# crossbar.net
KiCad netlist of a schematic drawn in Altium Designer
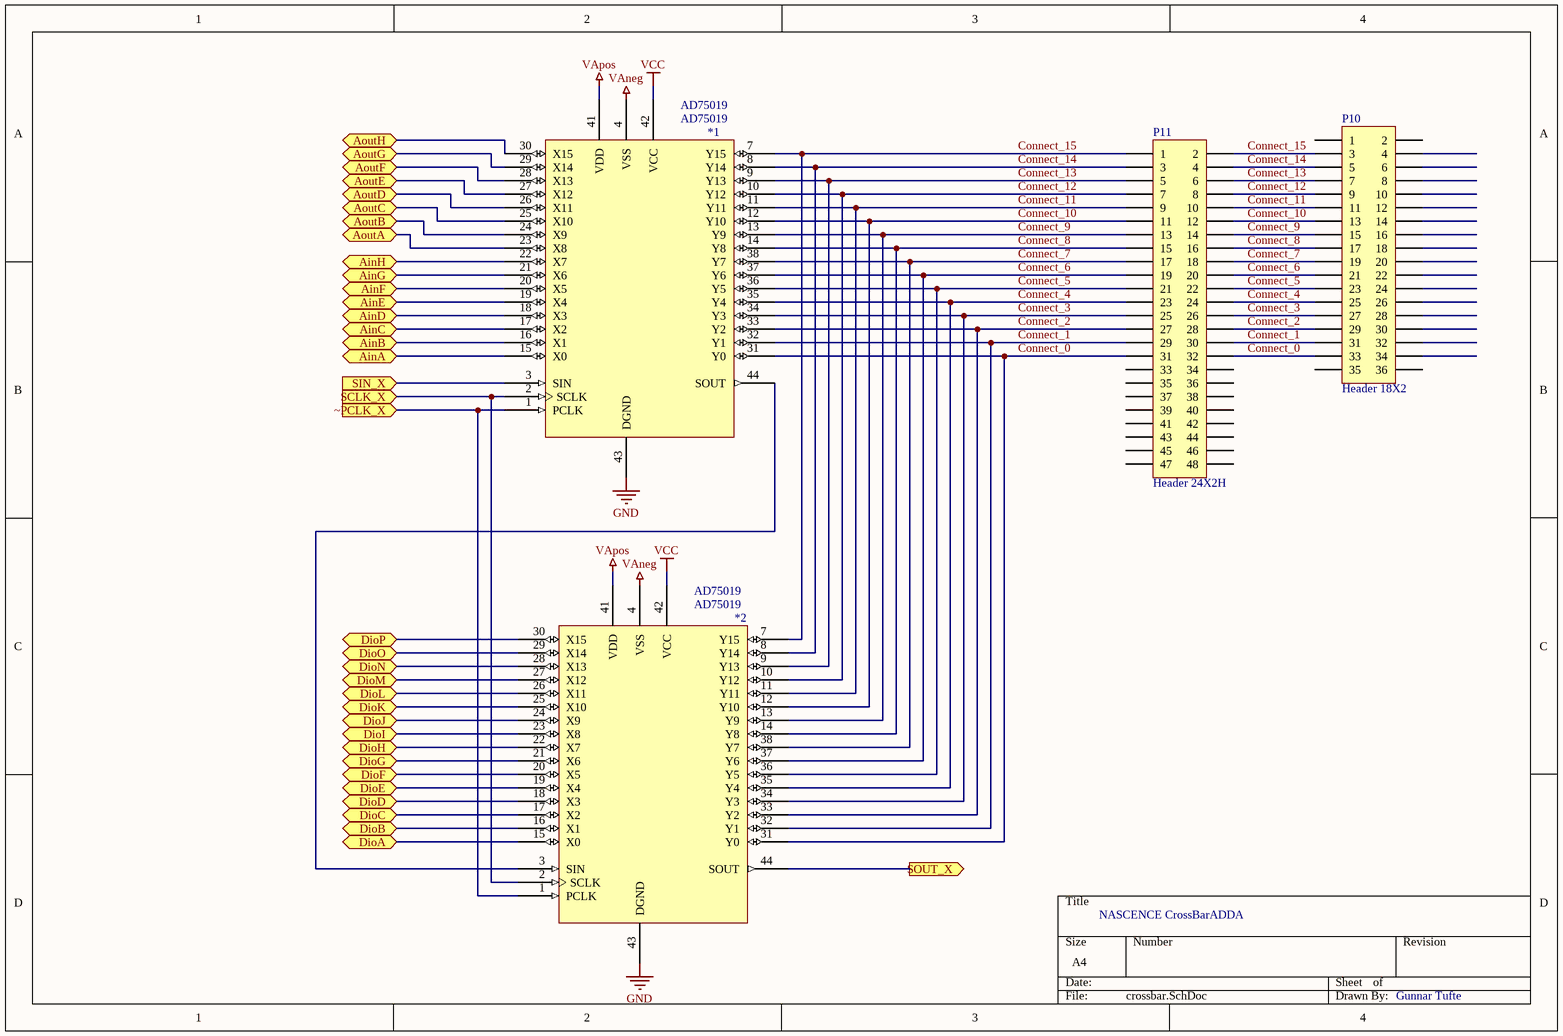
[diagram p0: crossbar.SchDoc]

(export (version "E")
  (design (tool "Eeschema 10.0.6"))
  (components
    (comp (ref "*1")
      (value "AD75019")
      (footprint "PLCC-44AL")
      (description "crosspoint 16x16")
      (fields (field (name "ALTIUM_UNNAMED_1") "AD75019"))
      (libsource (lib "GT_Schlib1") (part "Component_1"))
    )
    (comp (ref "*2")
      (value "AD75019")
      (footprint "PLCC-44AL")
      (description "crosspoint 16x16")
      (fields (field (name "ALTIUM_UNNAMED_1") "AD75019"))
      (libsource (lib "GT_Schlib1") (part "Component_1"))
    )
    (comp (ref "P10")
      (value "Header 18X2")
      (footprint "HDR2X18")
      (description "Header, 18-Pin, Dual row")
      (fields (field (name "PUBLISHER") "Altium Limited"))
      (libsource (lib "Miscellaneous Connectors") (part "Header 18X2"))
    )
    (comp (ref "P11")
      (value "Header 24X2H")
      (footprint "HDR2X24H")
      (description "Header, 24-Pin, Dual row, Right Angle")
      (fields (field (name "PUBLISHER") "Altium Limited"))
      (libsource (lib "Miscellaneous Connectors") (part "Header 24X2H"))
    )
  )
  (nets
    (net (code "1") (name "/AinA") (class "Default")
      (node (ref "*1") (pin "15") (pinfunction "X0_15") (pintype "bidirectional"))
    )
    (net (code "2") (name "/AinB") (class "Default")
      (node (ref "*1") (pin "16") (pinfunction "X1_16") (pintype "bidirectional"))
    )
    (net (code "3") (name "/AinC") (class "Default")
      (node (ref "*1") (pin "17") (pinfunction "X2_17") (pintype "bidirectional"))
    )
    (net (code "4") (name "/AinD") (class "Default")
      (node (ref "*1") (pin "18") (pinfunction "X3_18") (pintype "bidirectional"))
    )
    (net (code "5") (name "/AinE") (class "Default")
      (node (ref "*1") (pin "19") (pinfunction "X4_19") (pintype "bidirectional"))
    )
    (net (code "6") (name "/AinF") (class "Default")
      (node (ref "*1") (pin "20") (pinfunction "X5_20") (pintype "bidirectional"))
    )
    (net (code "7") (name "/AinG") (class "Default")
      (node (ref "*1") (pin "21") (pinfunction "X6_21") (pintype "bidirectional"))
    )
    (net (code "8") (name "/AinH") (class "Default")
      (node (ref "*1") (pin "22") (pinfunction "X7_22") (pintype "bidirectional"))
    )
    (net (code "9") (name "/AoutA") (class "Default")
      (node (ref "*1") (pin "23") (pinfunction "X8_23") (pintype "bidirectional"))
    )
    (net (code "10") (name "/AoutB") (class "Default")
      (node (ref "*1") (pin "24") (pinfunction "X9_24") (pintype "bidirectional"))
    )
    (net (code "11") (name "/AoutC") (class "Default")
      (node (ref "*1") (pin "25") (pinfunction "X10_25") (pintype "bidirectional"))
    )
    (net (code "12") (name "/AoutD") (class "Default")
      (node (ref "*1") (pin "26") (pinfunction "X11_26") (pintype "bidirectional"))
    )
    (net (code "13") (name "/AoutE") (class "Default")
      (node (ref "*1") (pin "27") (pinfunction "X12_27") (pintype "bidirectional"))
    )
    (net (code "14") (name "/AoutF") (class "Default")
      (node (ref "*1") (pin "28") (pinfunction "X13_28") (pintype "bidirectional"))
    )
    (net (code "15") (name "/AoutG") (class "Default")
      (node (ref "*1") (pin "29") (pinfunction "X14_29") (pintype "bidirectional"))
    )
    (net (code "16") (name "/AoutH") (class "Default")
      (node (ref "*1") (pin "30") (pinfunction "X15_30") (pintype "bidirectional"))
    )
    (net (code "17") (name "/Connect_0") (class "Default")
      (node (ref "*1") (pin "31") (pinfunction "Y0_31") (pintype "bidirectional"))
      (node (ref "*2") (pin "31") (pinfunction "Y0_31") (pintype "bidirectional"))
      (node (ref "P10") (pin "33") (pinfunction "33_33") (pintype "passive"))
      (node (ref "P11") (pin "31") (pinfunction "31_31") (pintype "passive"))
      (node (ref "P11") (pin "32") (pinfunction "32_32") (pintype "passive"))
    )
    (net (code "18") (name "/Connect_1") (class "Default")
      (node (ref "*1") (pin "32") (pinfunction "Y1_32") (pintype "bidirectional"))
      (node (ref "*2") (pin "32") (pinfunction "Y1_32") (pintype "bidirectional"))
      (node (ref "P10") (pin "31") (pinfunction "31_31") (pintype "passive"))
      (node (ref "P11") (pin "29") (pinfunction "29_29") (pintype "passive"))
      (node (ref "P11") (pin "30") (pinfunction "30_30") (pintype "passive"))
    )
    (net (code "19") (name "/Connect_2") (class "Default")
      (node (ref "*1") (pin "33") (pinfunction "Y2_33") (pintype "bidirectional"))
      (node (ref "*2") (pin "33") (pinfunction "Y2_33") (pintype "bidirectional"))
      (node (ref "P10") (pin "29") (pinfunction "29_29") (pintype "passive"))
      (node (ref "P11") (pin "27") (pinfunction "27_27") (pintype "passive"))
      (node (ref "P11") (pin "28") (pinfunction "28_28") (pintype "passive"))
    )
    (net (code "20") (name "/Connect_3") (class "Default")
      (node (ref "*1") (pin "34") (pinfunction "Y3_34") (pintype "bidirectional"))
      (node (ref "*2") (pin "34") (pinfunction "Y3_34") (pintype "bidirectional"))
      (node (ref "P10") (pin "27") (pinfunction "27_27") (pintype "passive"))
      (node (ref "P11") (pin "25") (pinfunction "25_25") (pintype "passive"))
      (node (ref "P11") (pin "26") (pinfunction "26_26") (pintype "passive"))
    )
    (net (code "21") (name "/Connect_4") (class "Default")
      (node (ref "*1") (pin "35") (pinfunction "Y4_35") (pintype "bidirectional"))
      (node (ref "*2") (pin "35") (pinfunction "Y4_35") (pintype "bidirectional"))
      (node (ref "P10") (pin "25") (pinfunction "25_25") (pintype "passive"))
      (node (ref "P11") (pin "23") (pinfunction "23_23") (pintype "passive"))
      (node (ref "P11") (pin "24") (pinfunction "24_24") (pintype "passive"))
    )
    (net (code "22") (name "/Connect_5") (class "Default")
      (node (ref "*1") (pin "36") (pinfunction "Y5_36") (pintype "bidirectional"))
      (node (ref "*2") (pin "36") (pinfunction "Y5_36") (pintype "bidirectional"))
      (node (ref "P10") (pin "23") (pinfunction "23_23") (pintype "passive"))
      (node (ref "P11") (pin "21") (pinfunction "21_21") (pintype "passive"))
      (node (ref "P11") (pin "22") (pinfunction "22_22") (pintype "passive"))
    )
    (net (code "23") (name "/Connect_6") (class "Default")
      (node (ref "*1") (pin "37") (pinfunction "Y6_37") (pintype "bidirectional"))
      (node (ref "*2") (pin "37") (pinfunction "Y6_37") (pintype "bidirectional"))
      (node (ref "P10") (pin "21") (pinfunction "21_21") (pintype "passive"))
      (node (ref "P11") (pin "19") (pinfunction "19_19") (pintype "passive"))
      (node (ref "P11") (pin "20") (pinfunction "20_20") (pintype "passive"))
    )
    (net (code "24") (name "/Connect_7") (class "Default")
      (node (ref "*1") (pin "38") (pinfunction "Y7_38") (pintype "bidirectional"))
      (node (ref "*2") (pin "38") (pinfunction "Y7_38") (pintype "bidirectional"))
      (node (ref "P10") (pin "19") (pinfunction "19_19") (pintype "passive"))
      (node (ref "P11") (pin "17") (pinfunction "17_17") (pintype "passive"))
      (node (ref "P11") (pin "18") (pinfunction "18_18") (pintype "passive"))
    )
    (net (code "25") (name "/Connect_8") (class "Default")
      (node (ref "*1") (pin "14") (pinfunction "Y8_14") (pintype "bidirectional"))
      (node (ref "*2") (pin "14") (pinfunction "Y8_14") (pintype "bidirectional"))
      (node (ref "P10") (pin "17") (pinfunction "17_17") (pintype "passive"))
      (node (ref "P11") (pin "15") (pinfunction "15_15") (pintype "passive"))
      (node (ref "P11") (pin "16") (pinfunction "16_16") (pintype "passive"))
    )
    (net (code "26") (name "/Connect_9") (class "Default")
      (node (ref "*1") (pin "13") (pinfunction "Y9_13") (pintype "bidirectional"))
      (node (ref "*2") (pin "13") (pinfunction "Y9_13") (pintype "bidirectional"))
      (node (ref "P10") (pin "15") (pinfunction "15_15") (pintype "passive"))
      (node (ref "P11") (pin "13") (pinfunction "13_13") (pintype "passive"))
      (node (ref "P11") (pin "14") (pinfunction "14_14") (pintype "passive"))
    )
    (net (code "27") (name "/Connect_10") (class "Default")
      (node (ref "*1") (pin "12") (pinfunction "Y10_12") (pintype "bidirectional"))
      (node (ref "*2") (pin "12") (pinfunction "Y10_12") (pintype "bidirectional"))
      (node (ref "P10") (pin "13") (pinfunction "13_13") (pintype "passive"))
      (node (ref "P11") (pin "11") (pinfunction "11_11") (pintype "passive"))
      (node (ref "P11") (pin "12") (pinfunction "12_12") (pintype "passive"))
    )
    (net (code "28") (name "/Connect_11") (class "Default")
      (node (ref "*1") (pin "11") (pinfunction "Y11_11") (pintype "bidirectional"))
      (node (ref "*2") (pin "11") (pinfunction "Y11_11") (pintype "bidirectional"))
      (node (ref "P10") (pin "11") (pinfunction "11_11") (pintype "passive"))
      (node (ref "P11") (pin "10") (pinfunction "10_10") (pintype "passive"))
      (node (ref "P11") (pin "9") (pinfunction "9_9") (pintype "passive"))
    )
    (net (code "29") (name "/Connect_12") (class "Default")
      (node (ref "*1") (pin "10") (pinfunction "Y12_10") (pintype "bidirectional"))
      (node (ref "*2") (pin "10") (pinfunction "Y12_10") (pintype "bidirectional"))
      (node (ref "P10") (pin "9") (pinfunction "9_9") (pintype "passive"))
      (node (ref "P11") (pin "7") (pinfunction "7_7") (pintype "passive"))
      (node (ref "P11") (pin "8") (pinfunction "8_8") (pintype "passive"))
    )
    (net (code "30") (name "/Connect_13") (class "Default")
      (node (ref "*1") (pin "9") (pinfunction "Y13_9") (pintype "bidirectional"))
      (node (ref "*2") (pin "9") (pinfunction "Y13_9") (pintype "bidirectional"))
      (node (ref "P10") (pin "7") (pinfunction "7_7") (pintype "passive"))
      (node (ref "P11") (pin "5") (pinfunction "5_5") (pintype "passive"))
      (node (ref "P11") (pin "6") (pinfunction "6_6") (pintype "passive"))
    )
    (net (code "31") (name "/Connect_14") (class "Default")
      (node (ref "*1") (pin "8") (pinfunction "Y14_8") (pintype "bidirectional"))
      (node (ref "*2") (pin "8") (pinfunction "Y14_8") (pintype "bidirectional"))
      (node (ref "P10") (pin "5") (pinfunction "5_5") (pintype "passive"))
      (node (ref "P11") (pin "3") (pinfunction "3_3") (pintype "passive"))
      (node (ref "P11") (pin "4") (pinfunction "4_4") (pintype "passive"))
    )
    (net (code "32") (name "/Connect_15") (class "Default")
      (node (ref "*1") (pin "7") (pinfunction "Y15_7") (pintype "bidirectional"))
      (node (ref "*2") (pin "7") (pinfunction "Y15_7") (pintype "bidirectional"))
      (node (ref "P10") (pin "3") (pinfunction "3_3") (pintype "passive"))
      (node (ref "P11") (pin "1") (pinfunction "1_1") (pintype "passive"))
      (node (ref "P11") (pin "2") (pinfunction "2_2") (pintype "passive"))
    )
    (net (code "33") (name "/DioA") (class "Default")
      (node (ref "*2") (pin "15") (pinfunction "X0_15") (pintype "bidirectional"))
    )
    (net (code "34") (name "/DioB") (class "Default")
      (node (ref "*2") (pin "16") (pinfunction "X1_16") (pintype "bidirectional"))
    )
    (net (code "35") (name "/DioC") (class "Default")
      (node (ref "*2") (pin "17") (pinfunction "X2_17") (pintype "bidirectional"))
    )
    (net (code "36") (name "/DioD") (class "Default")
      (node (ref "*2") (pin "18") (pinfunction "X3_18") (pintype "bidirectional"))
    )
    (net (code "37") (name "/DioE") (class "Default")
      (node (ref "*2") (pin "19") (pinfunction "X4_19") (pintype "bidirectional"))
    )
    (net (code "38") (name "/DioF") (class "Default")
      (node (ref "*2") (pin "20") (pinfunction "X5_20") (pintype "bidirectional"))
    )
    (net (code "39") (name "/DioG") (class "Default")
      (node (ref "*2") (pin "21") (pinfunction "X6_21") (pintype "bidirectional"))
    )
    (net (code "40") (name "/DioH") (class "Default")
      (node (ref "*2") (pin "22") (pinfunction "X7_22") (pintype "bidirectional"))
    )
    (net (code "41") (name "/DioI") (class "Default")
      (node (ref "*2") (pin "23") (pinfunction "X8_23") (pintype "bidirectional"))
    )
    (net (code "42") (name "/DioJ") (class "Default")
      (node (ref "*2") (pin "24") (pinfunction "X9_24") (pintype "bidirectional"))
    )
    (net (code "43") (name "/DioK") (class "Default")
      (node (ref "*2") (pin "25") (pinfunction "X10_25") (pintype "bidirectional"))
    )
    (net (code "44") (name "/DioL") (class "Default")
      (node (ref "*2") (pin "26") (pinfunction "X11_26") (pintype "bidirectional"))
    )
    (net (code "45") (name "/DioM") (class "Default")
      (node (ref "*2") (pin "27") (pinfunction "X12_27") (pintype "bidirectional"))
    )
    (net (code "46") (name "/DioN") (class "Default")
      (node (ref "*2") (pin "28") (pinfunction "X13_28") (pintype "bidirectional"))
    )
    (net (code "47") (name "/DioO") (class "Default")
      (node (ref "*2") (pin "29") (pinfunction "X14_29") (pintype "bidirectional"))
    )
    (net (code "48") (name "/DioP") (class "Default")
      (node (ref "*2") (pin "30") (pinfunction "X15_30") (pintype "bidirectional"))
    )
    (net (code "49") (name "/SCLK_X") (class "Default")
      (node (ref "*1") (pin "2") (pinfunction "SCLK_2") (pintype "input"))
      (node (ref "*2") (pin "2") (pinfunction "SCLK_2") (pintype "input"))
    )
    (net (code "50") (name "/SIN_X") (class "Default")
      (node (ref "*1") (pin "3") (pinfunction "SIN_3") (pintype "input"))
    )
    (net (code "51") (name "/SOUT_X") (class "Default")
      (node (ref "*2") (pin "44") (pinfunction "SOUT_44") (pintype "output"))
    )
    (net (code "52") (name "/~PCLK_X") (class "Default")
      (node (ref "*1") (pin "1") (pinfunction "PCLK_1") (pintype "input"))
      (node (ref "*2") (pin "1") (pinfunction "PCLK_1") (pintype "input"))
    )
    (net (code "53") (name "GND") (class "Default")
      (node (ref "*1") (pin "43") (pinfunction "DGND_43") (pintype "power_in"))
      (node (ref "*2") (pin "43") (pinfunction "DGND_43") (pintype "power_in"))
    )
    (net (code "54") (name "Net-(*1-SOUT)") (class "Default")
      (node (ref "*1") (pin "44") (pinfunction "SOUT_44") (pintype "output"))
      (node (ref "*2") (pin "3") (pinfunction "SIN_3") (pintype "input"))
    )
    (net (code "55") (name "VAneg") (class "Default")
      (node (ref "*1") (pin "4") (pinfunction "VSS_4") (pintype "power_in"))
      (node (ref "*2") (pin "4") (pinfunction "VSS_4") (pintype "power_in"))
    )
    (net (code "56") (name "VApos") (class "Default")
      (node (ref "*1") (pin "41") (pinfunction "VDD_41") (pintype "power_in"))
      (node (ref "*2") (pin "41") (pinfunction "VDD_41") (pintype "power_in"))
    )
    (net (code "57") (name "VCC") (class "Default")
      (node (ref "*1") (pin "42") (pinfunction "VCC_42") (pintype "power_in"))
      (node (ref "*2") (pin "42") (pinfunction "VCC_42") (pintype "power_in"))
    )
    (net (code "58") (name "unconnected-(*1-NC1-Pad5)") (class "Default")
      (node (ref "*1") (pin "5") (pinfunction "NC1_5") (pintype "passive"))
    )
    (net (code "59") (name "unconnected-(*1-NC2-Pad6)") (class "Default")
      (node (ref "*1") (pin "6") (pinfunction "NC2_6") (pintype "passive"))
    )
    (net (code "60") (name "unconnected-(*1-NC3-Pad39)") (class "Default")
      (node (ref "*1") (pin "39") (pinfunction "NC3_39") (pintype "passive"))
    )
    (net (code "61") (name "unconnected-(*1-NC4-Pad40)") (class "Default")
      (node (ref "*1") (pin "40") (pinfunction "NC4_40") (pintype "passive"))
    )
    (net (code "62") (name "unconnected-(*2-NC1-Pad5)") (class "Default")
      (node (ref "*2") (pin "5") (pinfunction "NC1_5") (pintype "passive"))
    )
    (net (code "63") (name "unconnected-(*2-NC2-Pad6)") (class "Default")
      (node (ref "*2") (pin "6") (pinfunction "NC2_6") (pintype "passive"))
    )
    (net (code "64") (name "unconnected-(*2-NC3-Pad39)") (class "Default")
      (node (ref "*2") (pin "39") (pinfunction "NC3_39") (pintype "passive"))
    )
    (net (code "65") (name "unconnected-(*2-NC4-Pad40)") (class "Default")
      (node (ref "*2") (pin "40") (pinfunction "NC4_40") (pintype "passive"))
    )
    (net (code "66") (name "unconnected-(P10-Pad1)") (class "Default")
      (node (ref "P10") (pin "1") (pinfunction "1_1") (pintype "passive"))
    )
    (net (code "67") (name "unconnected-(P10-Pad2)") (class "Default")
      (node (ref "P10") (pin "2") (pinfunction "2_2") (pintype "passive"))
    )
    (net (code "68") (name "unconnected-(P10-Pad4)") (class "Default")
      (node (ref "P10") (pin "4") (pinfunction "4_4") (pintype "passive"))
    )
    (net (code "69") (name "unconnected-(P10-Pad6)") (class "Default")
      (node (ref "P10") (pin "6") (pinfunction "6_6") (pintype "passive"))
    )
    (net (code "70") (name "unconnected-(P10-Pad8)") (class "Default")
      (node (ref "P10") (pin "8") (pinfunction "8_8") (pintype "passive"))
    )
    (net (code "71") (name "unconnected-(P10-Pad10)") (class "Default")
      (node (ref "P10") (pin "10") (pinfunction "10_10") (pintype "passive"))
    )
    (net (code "72") (name "unconnected-(P10-Pad12)") (class "Default")
      (node (ref "P10") (pin "12") (pinfunction "12_12") (pintype "passive"))
    )
    (net (code "73") (name "unconnected-(P10-Pad14)") (class "Default")
      (node (ref "P10") (pin "14") (pinfunction "14_14") (pintype "passive"))
    )
    (net (code "74") (name "unconnected-(P10-Pad16)") (class "Default")
      (node (ref "P10") (pin "16") (pinfunction "16_16") (pintype "passive"))
    )
    (net (code "75") (name "unconnected-(P10-Pad18)") (class "Default")
      (node (ref "P10") (pin "18") (pinfunction "18_18") (pintype "passive"))
    )
    (net (code "76") (name "unconnected-(P10-Pad20)") (class "Default")
      (node (ref "P10") (pin "20") (pinfunction "20_20") (pintype "passive"))
    )
    (net (code "77") (name "unconnected-(P10-Pad22)") (class "Default")
      (node (ref "P10") (pin "22") (pinfunction "22_22") (pintype "passive"))
    )
    (net (code "78") (name "unconnected-(P10-Pad24)") (class "Default")
      (node (ref "P10") (pin "24") (pinfunction "24_24") (pintype "passive"))
    )
    (net (code "79") (name "unconnected-(P10-Pad26)") (class "Default")
      (node (ref "P10") (pin "26") (pinfunction "26_26") (pintype "passive"))
    )
    (net (code "80") (name "unconnected-(P10-Pad28)") (class "Default")
      (node (ref "P10") (pin "28") (pinfunction "28_28") (pintype "passive"))
    )
    (net (code "81") (name "unconnected-(P10-Pad30)") (class "Default")
      (node (ref "P10") (pin "30") (pinfunction "30_30") (pintype "passive"))
    )
    (net (code "82") (name "unconnected-(P10-Pad32)") (class "Default")
      (node (ref "P10") (pin "32") (pinfunction "32_32") (pintype "passive"))
    )
    (net (code "83") (name "unconnected-(P10-Pad34)") (class "Default")
      (node (ref "P10") (pin "34") (pinfunction "34_34") (pintype "passive"))
    )
    (net (code "84") (name "unconnected-(P10-Pad35)") (class "Default")
      (node (ref "P10") (pin "35") (pinfunction "35_35") (pintype "passive"))
    )
    (net (code "85") (name "unconnected-(P10-Pad36)") (class "Default")
      (node (ref "P10") (pin "36") (pinfunction "36_36") (pintype "passive"))
    )
    (net (code "86") (name "unconnected-(P11-Pad33)") (class "Default")
      (node (ref "P11") (pin "33") (pinfunction "33_33") (pintype "passive"))
    )
    (net (code "87") (name "unconnected-(P11-Pad34)") (class "Default")
      (node (ref "P11") (pin "34") (pinfunction "34_34") (pintype "passive"))
    )
    (net (code "88") (name "unconnected-(P11-Pad35)") (class "Default")
      (node (ref "P11") (pin "35") (pinfunction "35_35") (pintype "passive"))
    )
    (net (code "89") (name "unconnected-(P11-Pad36)") (class "Default")
      (node (ref "P11") (pin "36") (pinfunction "36_36") (pintype "passive"))
    )
    (net (code "90") (name "unconnected-(P11-Pad37)") (class "Default")
      (node (ref "P11") (pin "37") (pinfunction "37_37") (pintype "passive"))
    )
    (net (code "91") (name "unconnected-(P11-Pad38)") (class "Default")
      (node (ref "P11") (pin "38") (pinfunction "38_38") (pintype "passive"))
    )
    (net (code "92") (name "unconnected-(P11-Pad39)") (class "Default")
      (node (ref "P11") (pin "39") (pinfunction "39_39") (pintype "passive"))
    )
    (net (code "93") (name "unconnected-(P11-Pad40)") (class "Default")
      (node (ref "P11") (pin "40") (pinfunction "40_40") (pintype "passive"))
    )
    (net (code "94") (name "unconnected-(P11-Pad41)") (class "Default")
      (node (ref "P11") (pin "41") (pinfunction "41_41") (pintype "passive"))
    )
    (net (code "95") (name "unconnected-(P11-Pad42)") (class "Default")
      (node (ref "P11") (pin "42") (pinfunction "42_42") (pintype "passive"))
    )
    (net (code "96") (name "unconnected-(P11-Pad43)") (class "Default")
      (node (ref "P11") (pin "43") (pinfunction "43_43") (pintype "passive"))
    )
    (net (code "97") (name "unconnected-(P11-Pad44)") (class "Default")
      (node (ref "P11") (pin "44") (pinfunction "44_44") (pintype "passive"))
    )
    (net (code "98") (name "unconnected-(P11-Pad45)") (class "Default")
      (node (ref "P11") (pin "45") (pinfunction "45_45") (pintype "passive"))
    )
    (net (code "99") (name "unconnected-(P11-Pad46)") (class "Default")
      (node (ref "P11") (pin "46") (pinfunction "46_46") (pintype "passive"))
    )
    (net (code "100") (name "unconnected-(P11-Pad47)") (class "Default")
      (node (ref "P11") (pin "47") (pinfunction "47_47") (pintype "passive"))
    )
    (net (code "101") (name "unconnected-(P11-Pad48)") (class "Default")
      (node (ref "P11") (pin "48") (pinfunction "48_48") (pintype "passive"))
    )
  )
)
